# dog.net
KiCad netlist of a schematic drawn in Altium Designer
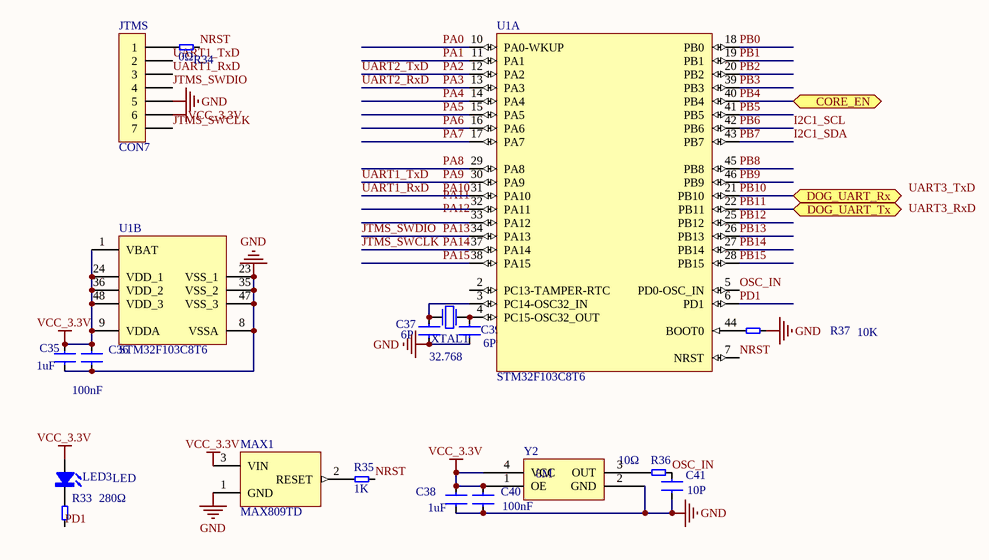
[diagram p0: dog.SchDoc]

(export (version "E")
  (design (tool "Eeschema 10.0.6"))
  (components
    (comp (ref "C35")
      (value "1uF")
      (footprint "0805/2012 C3")
      (description "105")
      (libsource (lib "标准元件库") (part "CAP4"))
    )
    (comp (ref "C36")
      (value "100nF")
      (footprint "0805/2012 C3")
      (description "104")
      (libsource (lib "标准元件库") (part "CAP4"))
    )
    (comp (ref "C37")
      (value "6P")
      (footprint "0805/2012 C3")
      (description "Capacitor")
      (libsource (lib "标准元件库") (part "CAP4"))
    )
    (comp (ref "C38")
      (value "1uF")
      (footprint "0805/2012 C3")
      (description "105")
      (libsource (lib "标准元件库") (part "CAP4"))
    )
    (comp (ref "C39")
      (value "6P")
      (footprint "0805/2012 C3")
      (description "Capacitor")
      (libsource (lib "标准元件库") (part "CAP4"))
    )
    (comp (ref "C40")
      (value "100nF")
      (footprint "0805/2012 C3")
      (description "104")
      (libsource (lib "标准元件库") (part "CAP4"))
    )
    (comp (ref "C41")
      (value "10P")
      (footprint "0805/2012 C3")
      (description "Capacitor")
      (libsource (lib "标准元件库") (part "CAP4"))
    )
    (comp (ref "JTMS")
      (value "CON7")
      (footprint "JTMS")
      (description "调试接口")
      (libsource (lib "Connector") (part "CON7"))
    )
    (comp (ref "LED3")
      (value "LED")
      (footprint "0805/2012 LEDB")
      (description "蓝")
      (libsource (lib "显示器件") (part "LED"))
    )
    (comp (ref "MAX1")
      (value "MAX809TD")
      (footprint "SOT-23 Q2")
      (description "复位芯片")
      (libsource (lib "单片机") (part "MAX809/810"))
    )
    (comp (ref "R33")
      (value "280Ω")
      (footprint "0805/2012 R3")
      (description "精度5%")
      (libsource (lib "标准元件库") (part "RES2"))
    )
    (comp (ref "R34")
      (value "0Ω")
      (footprint "0805/2012 R3")
      (description "精度5%")
      (libsource (lib "标准元件库") (part "RES2"))
    )
    (comp (ref "R35")
      (value "1K")
      (footprint "0805/2012 R3")
      (description "精度5%")
      (libsource (lib "标准元件库") (part "RES2"))
    )
    (comp (ref "R36")
      (value "10Ω")
      (footprint "0805/2012 R3")
      (description "精度5%")
      (libsource (lib "标准元件库") (part "RES2"))
    )
    (comp (ref "R37")
      (value "10K")
      (footprint "0805/2012 R3")
      (description "精度5%")
      (libsource (lib "标准元件库") (part "RES2"))
    )
    (comp (ref "U1")
      (value "STM32F103C8T6")
      (footprint "LQFP-48L")
      (libsource (lib "STM32") (part "STM32F103C8T6"))
    )
    (comp (ref "XTAL1")
      (value "32.768")
      (footprint "Y_3215-2")
      (description "32.768晶体")
      (libsource (lib "标准元件库") (part "XTAL"))
    )
    (comp (ref "Y2")
      (value "8M")
      (footprint "Y_3225-4")
      (description "8M有源晶振")
      (libsource (lib "标准元件库") (part "XTAL-SPXO"))
    )
  )
  (nets
    (net (code "1") (name "/I2C1_SCL") (class "Default")
      (node (ref "U1") (pin "42") (pinfunction "PB6_42") (pintype "bidirectional"))
    )
    (net (code "2") (name "/I2C1_SDA") (class "Default")
      (node (ref "U1") (pin "43") (pinfunction "PB7_43") (pintype "bidirectional"))
    )
    (net (code "3") (name "/JTMS_SWCLK") (class "Default")
      (node (ref "JTMS") (pin "7") (pinfunction "7_7") (pintype "passive"))
      (node (ref "U1") (pin "37") (pinfunction "PA14_37") (pintype "bidirectional"))
    )
    (net (code "4") (name "/JTMS_SWDIO") (class "Default")
      (node (ref "JTMS") (pin "4") (pinfunction "4_4") (pintype "passive"))
      (node (ref "U1") (pin "34") (pinfunction "PA13_34") (pintype "bidirectional"))
    )
    (net (code "5") (name "/NRST") (class "Default")
      (node (ref "R34") (pin "2") (pinfunction "2_2") (pintype "passive"))
      (node (ref "R35") (pin "2") (pinfunction "2_2") (pintype "passive"))
      (node (ref "U1") (pin "7") (pinfunction "NRST_7") (pintype "bidirectional"))
    )
    (net (code "6") (name "/OSC_IN") (class "Default")
      (node (ref "C41") (pin "2") (pinfunction "2_2") (pintype "passive"))
      (node (ref "R36") (pin "1") (pinfunction "1_1") (pintype "passive"))
      (node (ref "U1") (pin "5") (pinfunction "PD0-OSC_IN_5") (pintype "bidirectional"))
    )
    (net (code "7") (name "/PA0") (class "Default")
      (node (ref "U1") (pin "10") (pinfunction "PA0-WKUP_10") (pintype "bidirectional"))
    )
    (net (code "8") (name "/PA1") (class "Default")
      (node (ref "U1") (pin "11") (pinfunction "PA1_11") (pintype "bidirectional"))
    )
    (net (code "9") (name "/PA2") (class "Default")
      (node (ref "U1") (pin "12") (pinfunction "PA2_12") (pintype "bidirectional"))
    )
    (net (code "10") (name "/PA3") (class "Default")
      (node (ref "U1") (pin "13") (pinfunction "PA3_13") (pintype "bidirectional"))
    )
    (net (code "11") (name "/PA4") (class "Default")
      (node (ref "U1") (pin "14") (pinfunction "PA4_14") (pintype "bidirectional"))
    )
    (net (code "12") (name "/PA5") (class "Default")
      (node (ref "U1") (pin "15") (pinfunction "PA5_15") (pintype "bidirectional"))
    )
    (net (code "13") (name "/PA6") (class "Default")
      (node (ref "U1") (pin "16") (pinfunction "PA6_16") (pintype "bidirectional"))
    )
    (net (code "14") (name "/PA7") (class "Default")
      (node (ref "U1") (pin "17") (pinfunction "PA7_17") (pintype "bidirectional"))
    )
    (net (code "15") (name "/PA8") (class "Default")
      (node (ref "U1") (pin "29") (pinfunction "PA8_29") (pintype "bidirectional"))
    )
    (net (code "16") (name "/PA9") (class "Default")
      (node (ref "JTMS") (pin "2") (pinfunction "2_2") (pintype "passive"))
      (node (ref "U1") (pin "30") (pinfunction "PA9_30") (pintype "bidirectional"))
    )
    (net (code "17") (name "/PA10") (class "Default")
      (node (ref "JTMS") (pin "3") (pinfunction "3_3") (pintype "passive"))
      (node (ref "U1") (pin "31") (pinfunction "PA10_31") (pintype "bidirectional"))
    )
    (net (code "20") (name "/PA15") (class "Default")
      (node (ref "U1") (pin "38") (pinfunction "PA15_38") (pintype "bidirectional"))
    )
    (net (code "21") (name "/PB0") (class "Default")
      (node (ref "U1") (pin "18") (pinfunction "PB0_18") (pintype "bidirectional"))
    )
    (net (code "22") (name "/PB1") (class "Default")
      (node (ref "U1") (pin "19") (pinfunction "PB1_19") (pintype "bidirectional"))
    )
    (net (code "23") (name "/PB2") (class "Default")
      (node (ref "U1") (pin "20") (pinfunction "PB2_20") (pintype "bidirectional"))
    )
    (net (code "24") (name "/PB3") (class "Default")
      (node (ref "U1") (pin "39") (pinfunction "PB3_39") (pintype "bidirectional"))
    )
    (net (code "25") (name "/PB4") (class "Default")
      (node (ref "U1") (pin "40") (pinfunction "PB4_40") (pintype "bidirectional"))
    )
    (net (code "26") (name "/PB5") (class "Default")
      (node (ref "U1") (pin "41") (pinfunction "PB5_41") (pintype "bidirectional"))
    )
    (net (code "27") (name "/PB8") (class "Default")
      (node (ref "U1") (pin "45") (pinfunction "PB8_45") (pintype "bidirectional"))
    )
    (net (code "28") (name "/PB9") (class "Default")
      (node (ref "U1") (pin "46") (pinfunction "PB9_46") (pintype "bidirectional"))
    )
    (net (code "29") (name "/PB10") (class "Default")
      (node (ref "U1") (pin "21") (pinfunction "PB10_21") (pintype "bidirectional"))
    )
    (net (code "30") (name "/PB11") (class "Default")
      (node (ref "U1") (pin "22") (pinfunction "PB11_22") (pintype "bidirectional"))
    )
    (net (code "31") (name "/PB12") (class "Default")
      (node (ref "U1") (pin "25") (pinfunction "PB12_25") (pintype "bidirectional"))
    )
    (net (code "32") (name "/PB13") (class "Default")
      (node (ref "U1") (pin "26") (pinfunction "PB13_26") (pintype "bidirectional"))
    )
    (net (code "33") (name "/PB14") (class "Default")
      (node (ref "U1") (pin "27") (pinfunction "PB14_27") (pintype "bidirectional"))
    )
    (net (code "34") (name "/PB15") (class "Default")
      (node (ref "U1") (pin "28") (pinfunction "PB15_28") (pintype "bidirectional"))
    )
    (net (code "35") (name "/PD1") (class "Default")
      (node (ref "R33") (pin "2") (pinfunction "2_2") (pintype "passive"))
      (node (ref "U1") (pin "6") (pinfunction "PD1_6") (pintype "bidirectional"))
    )
    (net (code "38") (name "GND") (class "Default")
      (node (ref "C35") (pin "1") (pinfunction "1_1") (pintype "passive"))
      (node (ref "C36") (pin "1") (pinfunction "1_1") (pintype "passive"))
      (node (ref "C37") (pin "1") (pinfunction "1_1") (pintype "passive"))
      (node (ref "C38") (pin "1") (pinfunction "1_1") (pintype "passive"))
      (node (ref "C39") (pin "1") (pinfunction "1_1") (pintype "passive"))
      (node (ref "C40") (pin "1") (pinfunction "1_1") (pintype "passive"))
      (node (ref "C41") (pin "1") (pinfunction "1_1") (pintype "passive"))
      (node (ref "JTMS") (pin "5") (pinfunction "5_5") (pintype "passive"))
      (node (ref "MAX1") (pin "1") (pinfunction "GND_1") (pintype "power_in"))
      (node (ref "R37") (pin "2") (pinfunction "2_2") (pintype "passive"))
      (node (ref "U1") (pin "23") (pinfunction "VSS_1_23") (pintype "power_in"))
      (node (ref "U1") (pin "35") (pinfunction "VSS_2_35") (pintype "power_in"))
      (node (ref "U1") (pin "47") (pinfunction "VSS_3_47") (pintype "power_in"))
      (node (ref "U1") (pin "8") (pinfunction "VSSA_8") (pintype "power_in"))
      (node (ref "Y2") (pin "2") (pinfunction "GND_2") (pintype "passive"))
    )
    (net (code "39") (name "Net-(JTMS-Pad1)") (class "Default")
      (node (ref "JTMS") (pin "1") (pinfunction "1_1") (pintype "passive"))
      (node (ref "R34") (pin "1") (pinfunction "1_1") (pintype "passive"))
    )
    (net (code "40") (name "Net-(LED3-K)") (class "Default")
      (node (ref "LED3") (pin "2") (pinfunction "K_2") (pintype "passive"))
      (node (ref "R33") (pin "1") (pinfunction "1_1") (pintype "passive"))
    )
    (net (code "41") (name "Net-(MAX1-RESET)") (class "Default")
      (node (ref "MAX1") (pin "2") (pinfunction "RESET_2") (pintype "output"))
      (node (ref "R35") (pin "1") (pinfunction "1_1") (pintype "passive"))
    )
    (net (code "42") (name "Net-(U1A-BOOT0)") (class "Default")
      (node (ref "R37") (pin "1") (pinfunction "1_1") (pintype "passive"))
      (node (ref "U1") (pin "44") (pinfunction "BOOT0_44") (pintype "input"))
    )
    (net (code "43") (name "Net-(U1A-PC14-OSC32_IN)") (class "Default")
      (node (ref "C37") (pin "2") (pinfunction "2_2") (pintype "passive"))
      (node (ref "U1") (pin "3") (pinfunction "PC14-OSC32_IN_3") (pintype "bidirectional"))
      (node (ref "XTAL1") (pin "1") (pinfunction "P1_1") (pintype "passive"))
    )
    (net (code "44") (name "Net-(U1A-PC15-OSC32_OUT)") (class "Default")
      (node (ref "C39") (pin "2") (pinfunction "2_2") (pintype "passive"))
      (node (ref "U1") (pin "4") (pinfunction "PC15-OSC32_OUT_4") (pintype "bidirectional"))
      (node (ref "XTAL1") (pin "2") (pinfunction "P2_2") (pintype "passive"))
    )
    (net (code "45") (name "Net-(Y2-OUT)") (class "Default")
      (node (ref "R36") (pin "2") (pinfunction "2_2") (pintype "passive"))
      (node (ref "Y2") (pin "3") (pinfunction "OUT_3") (pintype "passive"))
    )
    (net (code "46") (name "VCC_3.3V") (class "Default")
      (node (ref "C35") (pin "2") (pinfunction "2_2") (pintype "passive"))
      (node (ref "C36") (pin "2") (pinfunction "2_2") (pintype "passive"))
      (node (ref "C38") (pin "2") (pinfunction "2_2") (pintype "passive"))
      (node (ref "C40") (pin "2") (pinfunction "2_2") (pintype "passive"))
      (node (ref "JTMS") (pin "6") (pinfunction "6_6") (pintype "passive"))
      (node (ref "LED3") (pin "1") (pinfunction "A_1") (pintype "passive"))
      (node (ref "MAX1") (pin "3") (pinfunction "VIN_3") (pintype "power_in"))
      (node (ref "U1") (pin "1") (pinfunction "VBAT_1") (pintype "power_in"))
      (node (ref "U1") (pin "24") (pinfunction "VDD_1_24") (pintype "power_in"))
      (node (ref "U1") (pin "36") (pinfunction "VDD_2_36") (pintype "power_in"))
      (node (ref "U1") (pin "48") (pinfunction "VDD_3_48") (pintype "power_in"))
      (node (ref "U1") (pin "9") (pinfunction "VDDA_9") (pintype "power_in"))
      (node (ref "Y2") (pin "1") (pinfunction "OE_1") (pintype "passive"))
      (node (ref "Y2") (pin "4") (pinfunction "VCC_4") (pintype "passive"))
    )
    (net (code "47") (name "unconnected-(U1A-PA11-Pad32)") (class "Default")
      (node (ref "U1") (pin "32") (pinfunction "PA11_32") (pintype "bidirectional"))
    )
    (net (code "48") (name "unconnected-(U1A-PA12-Pad33)") (class "Default")
      (node (ref "U1") (pin "33") (pinfunction "PA12_33") (pintype "bidirectional"))
    )
    (net (code "49") (name "unconnected-(U1A-PC13-TAMPER-RTC-Pad2)") (class "Default")
      (node (ref "U1") (pin "2") (pinfunction "PC13-TAMPER-RTC_2") (pintype "bidirectional"))
    )
  )
)
